# gerrit_lamp.net
KiCad netlist of a schematic drawn in EAGLE
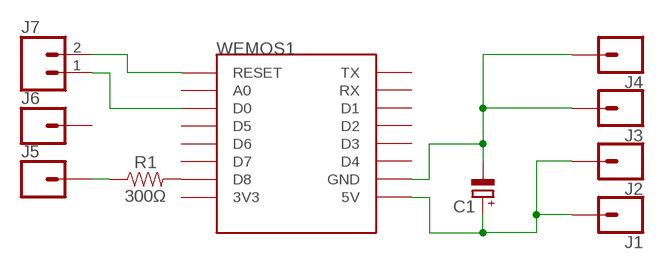
[diagram p0: schematic, sheet 1]

(export (version "E")
  (design (tool "Eeschema 10.0.6"))
  (components
    (comp (ref "C1")
      (value "CPOL-EUE5-5")
      (footprint "eagle-import:E5-5")
      (libsource (lib "eagle-import") (part "CPOL-EUE5-5"))
    )
    (comp (ref "J1")
      (value "CONN_01PTH_NO_SILK_KIT")
      (footprint "eagle-import:1X01NS_KIT")
      (libsource (lib "eagle-import") (part "CONN_01PTH_NO_SILK_KIT"))
    )
    (comp (ref "J2")
      (value "CONN_01PTH_NO_SILK_KIT")
      (footprint "eagle-import:1X01NS_KIT")
      (libsource (lib "eagle-import") (part "CONN_01PTH_NO_SILK_KIT"))
    )
    (comp (ref "J3")
      (value "CONN_01PTH_NO_SILK_KIT")
      (footprint "eagle-import:1X01NS_KIT")
      (libsource (lib "eagle-import") (part "CONN_01PTH_NO_SILK_KIT"))
    )
    (comp (ref "J4")
      (value "CONN_01PTH_NO_SILK_KIT")
      (footprint "eagle-import:1X01NS_KIT")
      (libsource (lib "eagle-import") (part "CONN_01PTH_NO_SILK_KIT"))
    )
    (comp (ref "J5")
      (value "CONN_01PTH_NO_SILK_KIT")
      (footprint "eagle-import:1X01NS_KIT")
      (libsource (lib "eagle-import") (part "CONN_01PTH_NO_SILK_KIT"))
    )
    (comp (ref "J6")
      (value "CONN_01PTH_NO_SILK_KIT")
      (footprint "eagle-import:1X01NS_KIT")
      (libsource (lib "eagle-import") (part "CONN_01PTH_NO_SILK_KIT"))
    )
    (comp (ref "J7")
      (value "CONN_02")
      (footprint "eagle-import:1X02")
      (libsource (lib "eagle-import") (part "CONN_02"))
    )
    (comp (ref "R1")
      (value "300Ω")
      (footprint "eagle-import:AXIAL-0.3")
      (libsource (lib "eagle-import") (part "RESISTORAXIAL-0.3"))
    )
    (comp (ref "WEMOS1")
      (value "WEMOS-D1-MINI")
      (footprint "eagle-import:WEMOS-D1-MINI")
      (libsource (lib "eagle-import") (part "WEMOS-D1-MINI"))
    )
  )
  (nets
    (net (code "1") (name "Net-(C1-Pad+)") (class "Default")
      (node (ref "C1") (pin "+") (pinfunction "+_+") (pintype "passive"))
      (node (ref "J1") (pin "1") (pinfunction "1_1") (pintype "passive"))
      (node (ref "J2") (pin "1") (pinfunction "1_1") (pintype "passive"))
      (node (ref "WEMOS1") (pin "5V") (pinfunction "5V_5V") (pintype "bidirectional"))
    )
    (net (code "2") (name "Net-(C1-Pad-)") (class "Default")
      (node (ref "C1") (pin "-") (pinfunction "-_-") (pintype "passive"))
      (node (ref "J3") (pin "1") (pinfunction "1_1") (pintype "passive"))
      (node (ref "J4") (pin "1") (pinfunction "1_1") (pintype "passive"))
      (node (ref "WEMOS1") (pin "GND") (pinfunction "GND_GND") (pintype "bidirectional"))
    )
    (net (code "3") (name "Net-(J7-Pad1)") (class "Default")
      (node (ref "J7") (pin "1") (pinfunction "1_1") (pintype "passive"))
      (node (ref "WEMOS1") (pin "D0") (pinfunction "D0_D0") (pintype "bidirectional"))
    )
    (net (code "4") (name "Net-(J7-Pad2)") (class "Default")
      (node (ref "J7") (pin "2") (pinfunction "2_2") (pintype "passive"))
      (node (ref "WEMOS1") (pin "RESET") (pinfunction "RESET_RESET") (pintype "bidirectional"))
    )
    (net (code "5") (name "Net-(R1-1)") (class "Default")
      (node (ref "J5") (pin "1") (pinfunction "1_1") (pintype "passive"))
      (node (ref "R1") (pin "P$1") (pinfunction "1_P$1") (pintype "passive"))
    )
    (net (code "6") (name "Net-(R1-2)") (class "Default")
      (node (ref "R1") (pin "P$2") (pinfunction "2_P$2") (pintype "passive"))
      (node (ref "WEMOS1") (pin "D8") (pinfunction "D8_D8") (pintype "bidirectional"))
    )
    (net (code "7") (name "unconnected-(J6-Pad1)") (class "Default")
      (node (ref "J6") (pin "1") (pinfunction "1_1") (pintype "passive"))
    )
    (net (code "8") (name "unconnected-(WEMOS1-Pad3V3)") (class "Default")
      (node (ref "WEMOS1") (pin "3V3") (pinfunction "3V3_3V3") (pintype "bidirectional"))
    )
    (net (code "9") (name "unconnected-(WEMOS1-PadA0)") (class "Default")
      (node (ref "WEMOS1") (pin "A0") (pinfunction "A0_A0") (pintype "bidirectional"))
    )
    (net (code "10") (name "unconnected-(WEMOS1-PadD1)") (class "Default")
      (node (ref "WEMOS1") (pin "D1") (pinfunction "D1_D1") (pintype "bidirectional"))
    )
    (net (code "11") (name "unconnected-(WEMOS1-PadD2)") (class "Default")
      (node (ref "WEMOS1") (pin "D2") (pinfunction "D2_D2") (pintype "bidirectional"))
    )
    (net (code "12") (name "unconnected-(WEMOS1-PadD3)") (class "Default")
      (node (ref "WEMOS1") (pin "D3") (pinfunction "D3_D3") (pintype "bidirectional"))
    )
    (net (code "13") (name "unconnected-(WEMOS1-PadD4)") (class "Default")
      (node (ref "WEMOS1") (pin "D4") (pinfunction "D4_D4") (pintype "bidirectional"))
    )
    (net (code "14") (name "unconnected-(WEMOS1-PadD5)") (class "Default")
      (node (ref "WEMOS1") (pin "D5") (pinfunction "D5_D5") (pintype "bidirectional"))
    )
    (net (code "15") (name "unconnected-(WEMOS1-PadD6)") (class "Default")
      (node (ref "WEMOS1") (pin "D6") (pinfunction "D6_D6") (pintype "bidirectional"))
    )
    (net (code "16") (name "unconnected-(WEMOS1-PadD7)") (class "Default")
      (node (ref "WEMOS1") (pin "D7") (pinfunction "D7_D7") (pintype "bidirectional"))
    )
    (net (code "17") (name "unconnected-(WEMOS1-PadRX)") (class "Default")
      (node (ref "WEMOS1") (pin "RX") (pinfunction "RX_RX") (pintype "bidirectional"))
    )
    (net (code "18") (name "unconnected-(WEMOS1-PadTX)") (class "Default")
      (node (ref "WEMOS1") (pin "TX") (pinfunction "TX_TX") (pintype "bidirectional"))
    )
  )
)
